# source_eagle.net
KiCad netlist of a schematic drawn in EAGLE
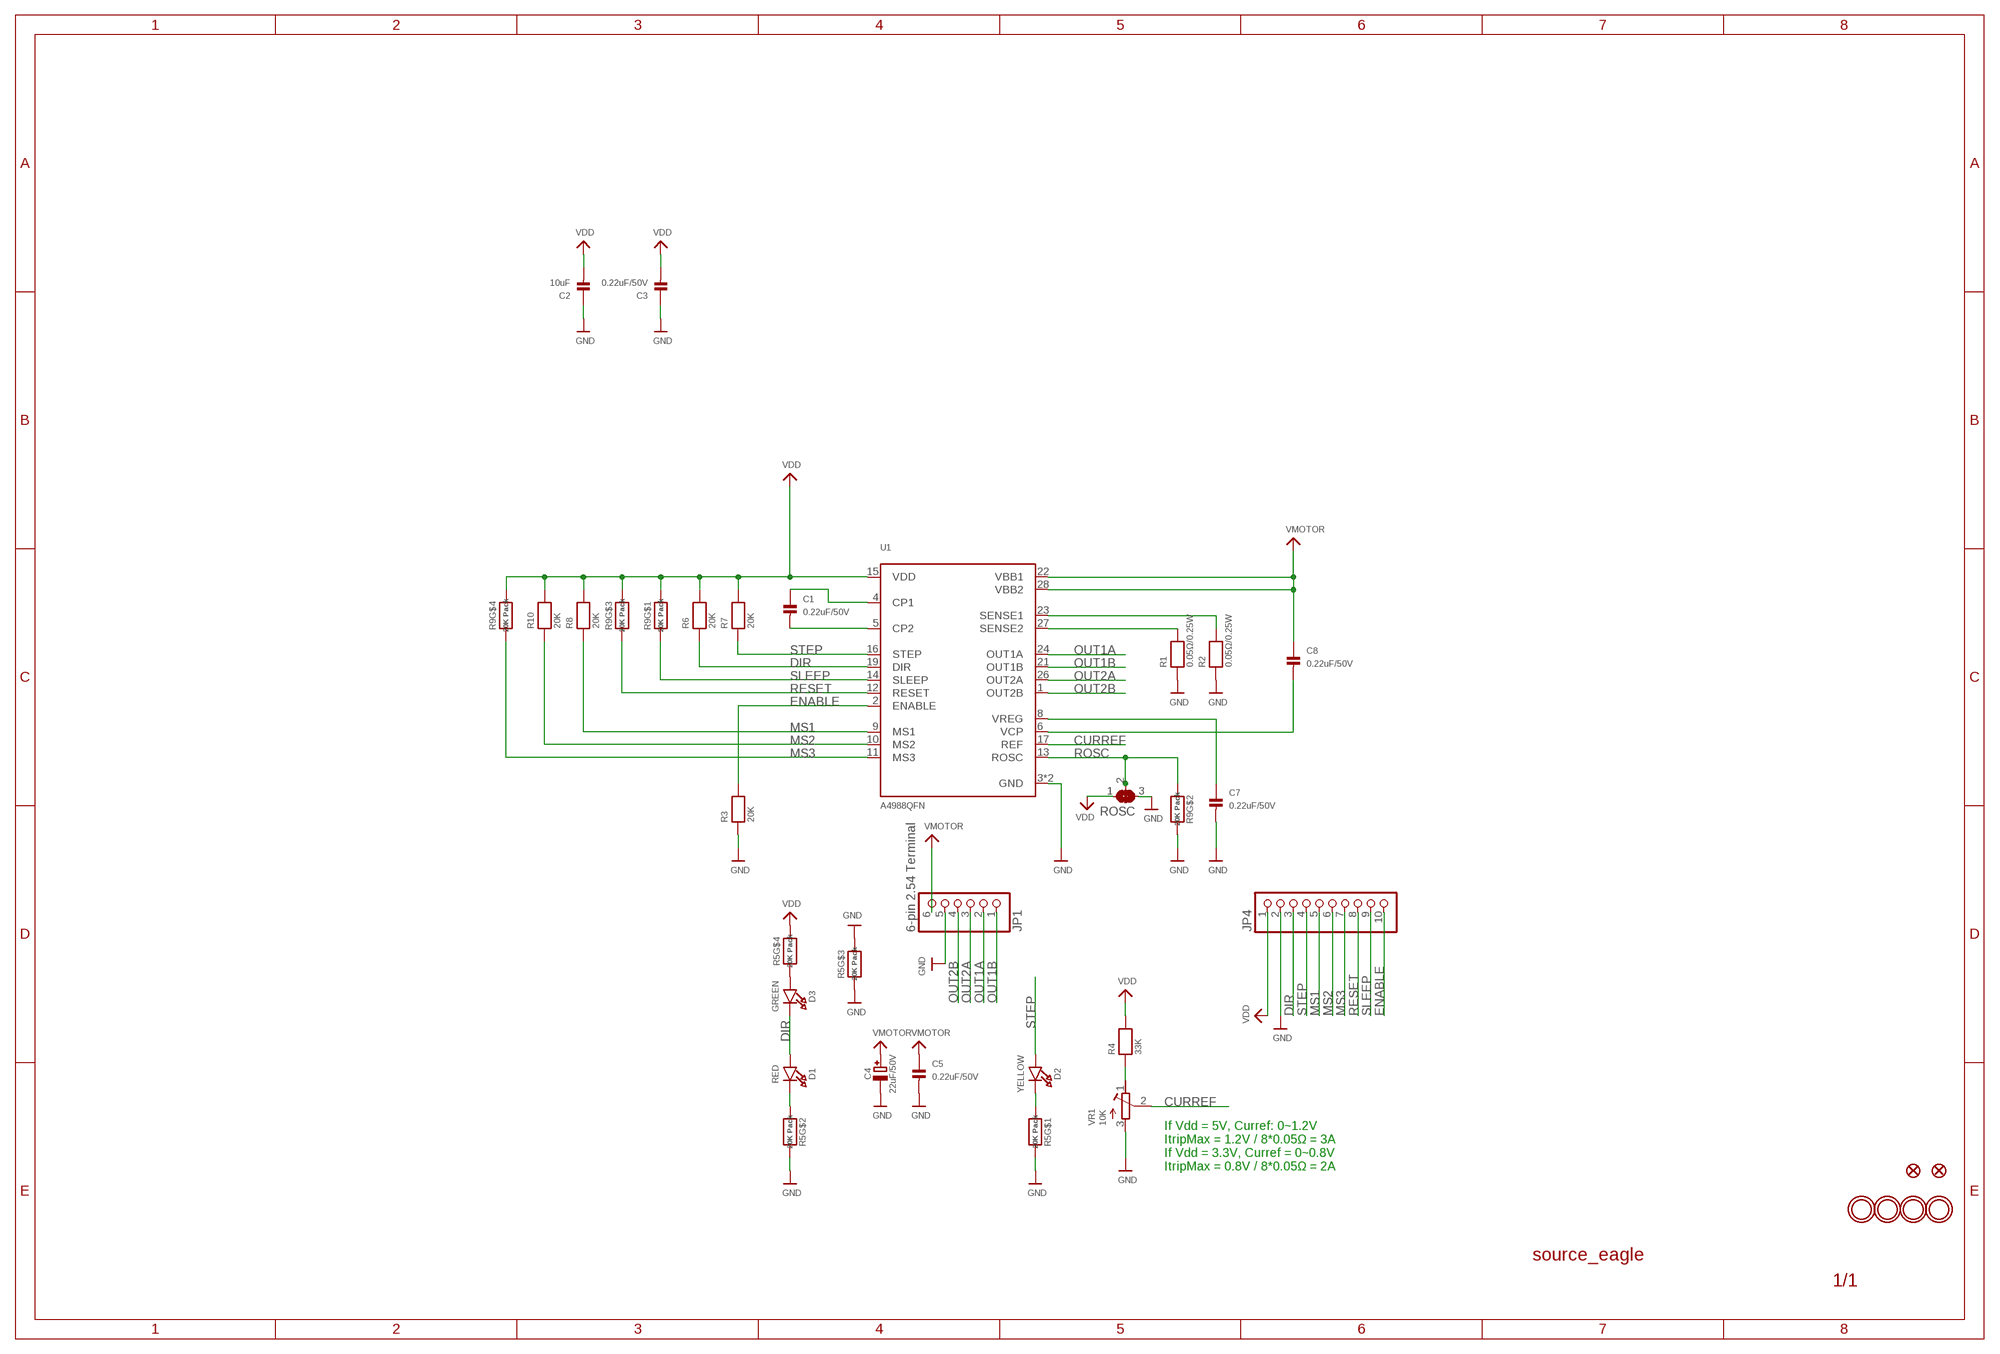
[diagram p0: schematic, sheet 1]

(export (version "E")
  (design (tool "Eeschema 10.0.6"))
  (components
    (comp (ref "C1")
      (value "0.22uF/50V")
      (footprint "eagle-import:0603-NO")
      (libsource (lib "eagle-import") (part "CAP_CERAMIC0603_NO"))
    )
    (comp (ref "C2")
      (value "10uF")
      (footprint "eagle-import:0805-NO")
      (libsource (lib "eagle-import") (part "CAP_CERAMIC0805-NOOUTLINE"))
    )
    (comp (ref "C3")
      (value "0.22uF/50V")
      (footprint "eagle-import:0603-NO")
      (libsource (lib "eagle-import") (part "CAP_CERAMIC0603_NO"))
    )
    (comp (ref "C4")
      (value "22uF/50V")
      (footprint "eagle-import:PANASONIC_C")
      (libsource (lib "eagle-import") (part "CAP_ELECTROLYTICPANASONIC_C"))
    )
    (comp (ref "C5")
      (value "0.22uF/50V")
      (footprint "eagle-import:0603-NO")
      (libsource (lib "eagle-import") (part "CAP_CERAMIC0603_NO"))
    )
    (comp (ref "C7")
      (value "0.22uF/50V")
      (footprint "eagle-import:0603-NO")
      (libsource (lib "eagle-import") (part "CAP_CERAMIC0603_NO"))
    )
    (comp (ref "C8")
      (value "0.22uF/50V")
      (footprint "eagle-import:0603-NO")
      (libsource (lib "eagle-import") (part "CAP_CERAMIC0603_NO"))
    )
    (comp (ref "D1")
      (value "RED")
      (footprint "eagle-import:CHIPLED_0603_NOOUTLINE")
      (libsource (lib "eagle-import") (part "LED0603_NOOUTLINE"))
    )
    (comp (ref "D2")
      (value "YELLOW")
      (footprint "eagle-import:CHIPLED_0603_NOOUTLINE")
      (libsource (lib "eagle-import") (part "LED0603_NOOUTLINE"))
    )
    (comp (ref "D3")
      (value "GREEN")
      (footprint "eagle-import:CHIPLED_0603_NOOUTLINE")
      (libsource (lib "eagle-import") (part "LED0603_NOOUTLINE"))
    )
    (comp (ref "JP1")
      (value "6-pin 2.54 Terminal")
      (footprint "eagle-import:1X06_2.54MMTERMINAL")
      (libsource (lib "eagle-import") (part "HEADER-1X6_2.54MMTERM"))
    )
    (comp (ref "JP4")
      (value "HEADER-1X1070MIL")
      (footprint "eagle-import:1X10_ROUND70")
      (libsource (lib "eagle-import") (part "HEADER-1X1070MIL"))
    )
    (comp (ref "R1")
      (value "0.05Ω/0.25W")
      (footprint "eagle-import:0603-NO")
      (libsource (lib "eagle-import") (part "RESISTOR_0603_NOOUT"))
    )
    (comp (ref "R2")
      (value "0.05Ω/0.25W")
      (footprint "eagle-import:0603-NO")
      (libsource (lib "eagle-import") (part "RESISTOR_0603_NOOUT"))
    )
    (comp (ref "R3")
      (value "20K")
      (footprint "eagle-import:0603-NO")
      (libsource (lib "eagle-import") (part "RESISTOR_0603_NOOUT"))
    )
    (comp (ref "R4")
      (value "33K")
      (footprint "eagle-import:0603-NO")
      (libsource (lib "eagle-import") (part "RESISTOR_0603_NOOUT"))
    )
    (comp (ref "R5")
      (value "20K Pack")
      (footprint "eagle-import:RESPACK_4X0603")
      (libsource (lib "eagle-import") (part "RESISTOR_4PACK"))
    )
    (comp (ref "R6")
      (value "20K")
      (footprint "eagle-import:0603-NO")
      (libsource (lib "eagle-import") (part "RESISTOR_0603_NOOUT"))
    )
    (comp (ref "R7")
      (value "20K")
      (footprint "eagle-import:0603-NO")
      (libsource (lib "eagle-import") (part "RESISTOR_0603_NOOUT"))
    )
    (comp (ref "R8")
      (value "20K")
      (footprint "eagle-import:0603-NO")
      (libsource (lib "eagle-import") (part "RESISTOR_0603_NOOUT"))
    )
    (comp (ref "R9")
      (value "20K Pack")
      (footprint "eagle-import:RESPACK_4X0603")
      (libsource (lib "eagle-import") (part "RESISTOR_4PACK"))
    )
    (comp (ref "R10")
      (value "20K")
      (footprint "eagle-import:0603-NO")
      (libsource (lib "eagle-import") (part "RESISTOR_0603_NOOUT"))
    )
    (comp (ref "ROSC")
      (value "SOLDERJUMPER_2WAY")
      (footprint "eagle-import:SOLDERJUMPER_2WAY_OPEN_NOPASTE")
      (libsource (lib "eagle-import") (part "SOLDERJUMPER_2WAY"))
    )
    (comp (ref "U$10")
      (value "FIDUCIAL_0.5MM")
      (footprint "eagle-import:FIDUCIAL_0.5MM")
      (libsource (lib "eagle-import") (part "FIDUCIAL_0.5MM"))
    )
    (comp (ref "U$11")
      (value "FIDUCIAL_0.5MM")
      (footprint "eagle-import:FIDUCIAL_0.5MM")
      (libsource (lib "eagle-import") (part "FIDUCIAL_0.5MM"))
    )
    (comp (ref "U$18")
      (value "MOUNTINGHOLE2.0")
      (footprint "eagle-import:MOUNTINGHOLE_2.0_PLATED")
      (libsource (lib "eagle-import") (part "MOUNTINGHOLE2.0"))
    )
    (comp (ref "U$22")
      (value "MOUNTINGHOLE2.0")
      (footprint "eagle-import:MOUNTINGHOLE_2.0_PLATED")
      (libsource (lib "eagle-import") (part "MOUNTINGHOLE2.0"))
    )
    (comp (ref "U$26")
      (value "MOUNTINGHOLE2.0")
      (footprint "eagle-import:MOUNTINGHOLE_2.0_PLATED")
      (libsource (lib "eagle-import") (part "MOUNTINGHOLE2.0"))
    )
    (comp (ref "U$27")
      (value "MOUNTINGHOLE2.0")
      (footprint "eagle-import:MOUNTINGHOLE_2.0_PLATED")
      (libsource (lib "eagle-import") (part "MOUNTINGHOLE2.0"))
    )
    (comp (ref "U1")
      (value "A4988QFN")
      (footprint "eagle-import:QFN28_5MM")
      (libsource (lib "eagle-import") (part "A4983_LOGICAL"))
    )
    (comp (ref "VR1")
      (value "10K")
      (footprint "eagle-import:RTRIM3314J")
      (libsource (lib "eagle-import") (part "R-TRIMM3314J"))
    )
  )
  (nets
    (net (code "1") (name "/CURREF") (class "Default")
      (node (ref "U1") (pin "17") (pinfunction "REF_17") (pintype "bidirectional"))
      (node (ref "VR1") (pin "2") (pinfunction "S_2") (pintype "passive"))
    )
    (net (code "2") (name "/DIR") (class "Default")
      (node (ref "D1") (pin "A") (pinfunction "A_A") (pintype "passive"))
      (node (ref "D3") (pin "C") (pinfunction "C_C") (pintype "passive"))
      (node (ref "JP4") (pin "3") (pinfunction "3_3") (pintype "passive"))
      (node (ref "R6") (pin "1") (pinfunction "1_1") (pintype "passive"))
      (node (ref "U1") (pin "19") (pinfunction "DIR_19") (pintype "input"))
    )
    (net (code "3") (name "/ENABLE") (class "Default")
      (node (ref "JP4") (pin "10") (pinfunction "10_10") (pintype "passive"))
      (node (ref "R3") (pin "2") (pinfunction "2_2") (pintype "passive"))
      (node (ref "U1") (pin "2") (pinfunction "ENABLE_2") (pintype "input"))
    )
    (net (code "4") (name "/MS1") (class "Default")
      (node (ref "JP4") (pin "5") (pinfunction "5_5") (pintype "passive"))
      (node (ref "R8") (pin "1") (pinfunction "1_1") (pintype "passive"))
      (node (ref "U1") (pin "9") (pinfunction "MS1_9") (pintype "input"))
    )
    (net (code "5") (name "/MS2") (class "Default")
      (node (ref "JP4") (pin "6") (pinfunction "6_6") (pintype "passive"))
      (node (ref "R10") (pin "1") (pinfunction "1_1") (pintype "passive"))
      (node (ref "U1") (pin "10") (pinfunction "MS2_10") (pintype "input"))
    )
    (net (code "6") (name "/MS3") (class "Default")
      (node (ref "JP4") (pin "7") (pinfunction "7_7") (pintype "passive"))
      (node (ref "R9") (pin "4") (pinfunction "1_4") (pintype "passive"))
      (node (ref "U1") (pin "11") (pinfunction "MS3_11") (pintype "input"))
    )
    (net (code "7") (name "/OUT1A") (class "Default")
      (node (ref "JP1") (pin "2") (pinfunction "2_2") (pintype "passive"))
      (node (ref "U1") (pin "24") (pinfunction "OUT1A_24") (pintype "bidirectional"))
    )
    (net (code "8") (name "/OUT1B") (class "Default")
      (node (ref "JP1") (pin "1") (pinfunction "1_1") (pintype "passive"))
      (node (ref "U1") (pin "21") (pinfunction "OUT1B_21") (pintype "bidirectional"))
    )
    (net (code "9") (name "/OUT2A") (class "Default")
      (node (ref "JP1") (pin "3") (pinfunction "3_3") (pintype "passive"))
      (node (ref "U1") (pin "26") (pinfunction "OUT2A_26") (pintype "bidirectional"))
    )
    (net (code "10") (name "/OUT2B") (class "Default")
      (node (ref "JP1") (pin "4") (pinfunction "4_4") (pintype "passive"))
      (node (ref "U1") (pin "1") (pinfunction "OUT2B_1") (pintype "bidirectional"))
    )
    (net (code "11") (name "/RESET") (class "Default")
      (node (ref "JP4") (pin "8") (pinfunction "8_8") (pintype "passive"))
      (node (ref "R9") (pin "3") (pinfunction "1_3") (pintype "passive"))
      (node (ref "U1") (pin "12") (pinfunction "RESET_12") (pintype "input"))
    )
    (net (code "12") (name "/ROSC") (class "Default")
      (node (ref "R9") (pin "2") (pinfunction "1_2") (pintype "passive"))
      (node (ref "ROSC") (pin "2") (pinfunction "2_2") (pintype "passive"))
      (node (ref "U1") (pin "13") (pinfunction "ROSC_13") (pintype "bidirectional"))
    )
    (net (code "13") (name "/SLEEP") (class "Default")
      (node (ref "JP4") (pin "9") (pinfunction "9_9") (pintype "passive"))
      (node (ref "R9") (pin "1") (pinfunction "1_1") (pintype "passive"))
      (node (ref "U1") (pin "14") (pinfunction "SLEEP_14") (pintype "bidirectional"))
    )
    (net (code "14") (name "/STEP") (class "Default")
      (node (ref "D2") (pin "A") (pinfunction "A_A") (pintype "passive"))
      (node (ref "JP4") (pin "4") (pinfunction "4_4") (pintype "passive"))
      (node (ref "R7") (pin "1") (pinfunction "1_1") (pintype "passive"))
      (node (ref "U1") (pin "16") (pinfunction "STEP_16") (pintype "input"))
    )
    (net (code "15") (name "GND") (class "Default")
      (node (ref "C2") (pin "1") (pinfunction "1_1") (pintype "passive"))
      (node (ref "C3") (pin "1") (pinfunction "1_1") (pintype "passive"))
      (node (ref "C4") (pin "-") (pinfunction "-_-") (pintype "passive"))
      (node (ref "C5") (pin "2") (pinfunction "2_2") (pintype "passive"))
      (node (ref "C7") (pin "2") (pinfunction "2_2") (pintype "passive"))
      (node (ref "JP1") (pin "5") (pinfunction "5_5") (pintype "passive"))
      (node (ref "JP4") (pin "2") (pinfunction "2_2") (pintype "passive"))
      (node (ref "R1") (pin "1") (pinfunction "1_1") (pintype "passive"))
      (node (ref "R2") (pin "1") (pinfunction "1_1") (pintype "passive"))
      (node (ref "R3") (pin "1") (pinfunction "1_1") (pintype "passive"))
      (node (ref "R5") (pin "3") (pinfunction "1_3") (pintype "passive"))
      (node (ref "R5") (pin "6") (pinfunction "2_6") (pintype "passive"))
      (node (ref "R5") (pin "7") (pinfunction "2_7") (pintype "passive"))
      (node (ref "R5") (pin "8") (pinfunction "2_8") (pintype "passive"))
      (node (ref "R9") (pin "7") (pinfunction "2_7") (pintype "passive"))
      (node (ref "ROSC") (pin "3") (pinfunction "3_3") (pintype "passive"))
      (node (ref "U1") (pin "3") (pinfunction "GND_3") (pintype "power_in"))
      (node (ref "U1") (pin "THERMAL") (pinfunction "GND_THERMAL") (pintype "power_in"))
      (node (ref "VR1") (pin "3") (pinfunction "A_3") (pintype "passive"))
    )
    (net (code "16") (name "Net-(D2-PadC)") (class "Default")
      (node (ref "D2") (pin "C") (pinfunction "C_C") (pintype "passive"))
      (node (ref "R5") (pin "1") (pinfunction "1_1") (pintype "passive"))
    )
    (net (code "17") (name "Net-(R5B-1)") (class "Default")
      (node (ref "D1") (pin "C") (pinfunction "C_C") (pintype "passive"))
      (node (ref "R5") (pin "2") (pinfunction "1_2") (pintype "passive"))
    )
    (net (code "18") (name "Net-(R5D-1)") (class "Default")
      (node (ref "D3") (pin "A") (pinfunction "A_A") (pintype "passive"))
      (node (ref "R5") (pin "4") (pinfunction "1_4") (pintype "passive"))
    )
    (net (code "19") (name "Net-(U1-CP1)") (class "Default")
      (node (ref "C1") (pin "1") (pinfunction "1_1") (pintype "passive"))
      (node (ref "U1") (pin "4") (pinfunction "CP1_4") (pintype "bidirectional"))
    )
    (net (code "20") (name "Net-(U1-CP2)") (class "Default")
      (node (ref "C1") (pin "2") (pinfunction "2_2") (pintype "passive"))
      (node (ref "U1") (pin "5") (pinfunction "CP2_5") (pintype "bidirectional"))
    )
    (net (code "21") (name "Net-(U1-SENSE1)") (class "Default")
      (node (ref "R2") (pin "2") (pinfunction "2_2") (pintype "passive"))
      (node (ref "U1") (pin "23") (pinfunction "SENSE1_23") (pintype "bidirectional"))
    )
    (net (code "22") (name "Net-(U1-SENSE2)") (class "Default")
      (node (ref "R1") (pin "2") (pinfunction "2_2") (pintype "passive"))
      (node (ref "U1") (pin "27") (pinfunction "SENSE2_27") (pintype "bidirectional"))
    )
    (net (code "23") (name "Net-(U1-VCP)") (class "Default")
      (node (ref "C8") (pin "2") (pinfunction "2_2") (pintype "passive"))
      (node (ref "U1") (pin "6") (pinfunction "VCP_6") (pintype "bidirectional"))
    )
    (net (code "24") (name "Net-(U1-VREG)") (class "Default")
      (node (ref "C7") (pin "1") (pinfunction "1_1") (pintype "passive"))
      (node (ref "U1") (pin "8") (pinfunction "VREG_8") (pintype "bidirectional"))
    )
    (net (code "25") (name "Net-(VR1-E)") (class "Default")
      (node (ref "R4") (pin "1") (pinfunction "1_1") (pintype "passive"))
      (node (ref "VR1") (pin "1") (pinfunction "E_1") (pintype "passive"))
    )
    (net (code "26") (name "VDD") (class "Default")
      (node (ref "C2") (pin "2") (pinfunction "2_2") (pintype "passive"))
      (node (ref "C3") (pin "2") (pinfunction "2_2") (pintype "passive"))
      (node (ref "JP4") (pin "1") (pinfunction "1_1") (pintype "passive"))
      (node (ref "R10") (pin "2") (pinfunction "2_2") (pintype "passive"))
      (node (ref "R4") (pin "2") (pinfunction "2_2") (pintype "passive"))
      (node (ref "R5") (pin "5") (pinfunction "2_5") (pintype "passive"))
      (node (ref "R6") (pin "2") (pinfunction "2_2") (pintype "passive"))
      (node (ref "R7") (pin "2") (pinfunction "2_2") (pintype "passive"))
      (node (ref "R8") (pin "2") (pinfunction "2_2") (pintype "passive"))
      (node (ref "R9") (pin "5") (pinfunction "2_5") (pintype "passive"))
      (node (ref "R9") (pin "6") (pinfunction "2_6") (pintype "passive"))
      (node (ref "R9") (pin "8") (pinfunction "2_8") (pintype "passive"))
      (node (ref "ROSC") (pin "1") (pinfunction "1_1") (pintype "passive"))
      (node (ref "U1") (pin "15") (pinfunction "VDD_15") (pintype "power_in"))
    )
    (net (code "27") (name "VMOTOR") (class "Default")
      (node (ref "C4") (pin "+") (pinfunction "+_+") (pintype "passive"))
      (node (ref "C5") (pin "1") (pinfunction "1_1") (pintype "passive"))
      (node (ref "C8") (pin "1") (pinfunction "1_1") (pintype "passive"))
      (node (ref "JP1") (pin "6") (pinfunction "6_6") (pintype "passive"))
      (node (ref "U1") (pin "22") (pinfunction "VBB1_22") (pintype "bidirectional"))
      (node (ref "U1") (pin "28") (pinfunction "VBB2_28") (pintype "bidirectional"))
    )
  )
)
